# DOE_PCB_Schematics.net
KiCad netlist of a schematic drawn in EAGLE
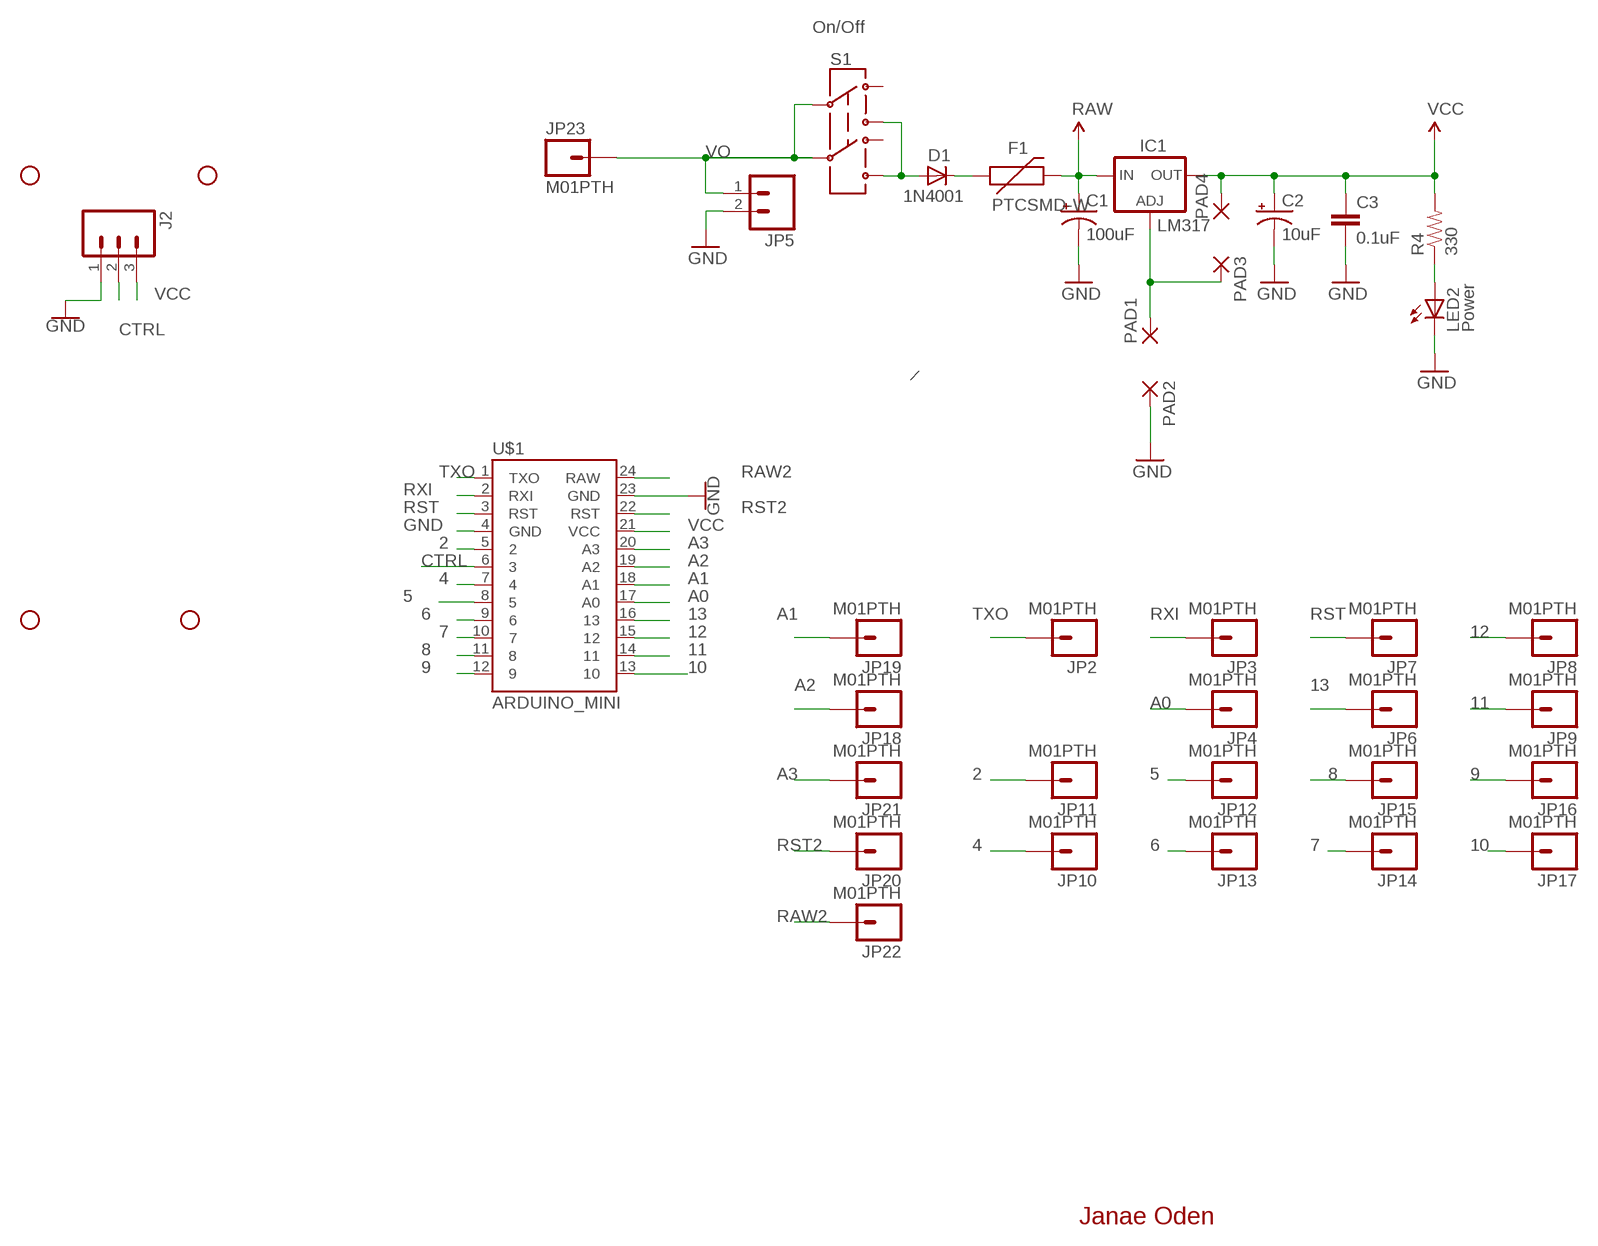
[diagram p0: schematic, sheet 1]

(export (version "E")
  (design (tool "Eeschema 10.0.6"))
  (components
    (comp (ref "C1")
      (value "100uF")
      (footprint "eagle-import:EIA7343")
      (libsource (lib "eagle-import") (part "CAP_POL7343"))
    )
    (comp (ref "C2")
      (value "10uF")
      (footprint "eagle-import:EIA3216")
      (libsource (lib "eagle-import") (part "CAP_POL1206"))
    )
    (comp (ref "C3")
      (value "0.1uF")
      (footprint "eagle-import:0603-CAP")
      (libsource (lib "eagle-import") (part "CAP0603-CAP"))
    )
    (comp (ref "D1")
      (value "1N4001")
      (footprint "eagle-import:SMA-DIODE-TYLERALT1")
      (libsource (lib "eagle-import") (part "DIODESMA-TYLERALT1"))
    )
    (comp (ref "F1")
      (value "PTCSMD-W")
      (footprint "eagle-import:PTC-1206-WIDE")
      (libsource (lib "eagle-import") (part "PTCSMD-W"))
    )
    (comp (ref "IC1")
      (value "LM317MBSTT3")
      (footprint "eagle-import:SOT223")
      (fields (field (name "PARTNUMBER") "LM317"))
      (libsource (lib "eagle-import") (part "LM317?MBSTT3"))
    )
    (comp (ref "J2")
      (value "M03SCREW")
      (footprint "eagle-import:SCREWTERMINAL-3.5MM-3")
      (libsource (lib "eagle-import") (part "M03SCREW"))
    )
    (comp (ref "JP2")
      (value "M01PTH")
      (footprint "eagle-import:1X01")
      (libsource (lib "eagle-import") (part "M01PTH"))
    )
    (comp (ref "JP3")
      (value "M01PTH")
      (footprint "eagle-import:1X01")
      (libsource (lib "eagle-import") (part "M01PTH"))
    )
    (comp (ref "JP4")
      (value "M01PTH")
      (footprint "eagle-import:1X01")
      (libsource (lib "eagle-import") (part "M01PTH"))
    )
    (comp (ref "JP5")
      (value "M02PTH")
      (footprint "eagle-import:1X02")
      (libsource (lib "eagle-import") (part "M02PTH"))
    )
    (comp (ref "JP6")
      (value "M01PTH")
      (footprint "eagle-import:1X01")
      (libsource (lib "eagle-import") (part "M01PTH"))
    )
    (comp (ref "JP7")
      (value "M01PTH")
      (footprint "eagle-import:1X01")
      (libsource (lib "eagle-import") (part "M01PTH"))
    )
    (comp (ref "JP8")
      (value "M01PTH")
      (footprint "eagle-import:1X01")
      (libsource (lib "eagle-import") (part "M01PTH"))
    )
    (comp (ref "JP9")
      (value "M01PTH")
      (footprint "eagle-import:1X01")
      (libsource (lib "eagle-import") (part "M01PTH"))
    )
    (comp (ref "JP10")
      (value "M01PTH")
      (footprint "eagle-import:1X01")
      (libsource (lib "eagle-import") (part "M01PTH"))
    )
    (comp (ref "JP11")
      (value "M01PTH")
      (footprint "eagle-import:1X01")
      (libsource (lib "eagle-import") (part "M01PTH"))
    )
    (comp (ref "JP12")
      (value "M01PTH")
      (footprint "eagle-import:1X01")
      (libsource (lib "eagle-import") (part "M01PTH"))
    )
    (comp (ref "JP13")
      (value "M01PTH")
      (footprint "eagle-import:1X01")
      (libsource (lib "eagle-import") (part "M01PTH"))
    )
    (comp (ref "JP14")
      (value "M01PTH")
      (footprint "eagle-import:1X01")
      (libsource (lib "eagle-import") (part "M01PTH"))
    )
    (comp (ref "JP15")
      (value "M01PTH")
      (footprint "eagle-import:1X01")
      (libsource (lib "eagle-import") (part "M01PTH"))
    )
    (comp (ref "JP16")
      (value "M01PTH")
      (footprint "eagle-import:1X01")
      (libsource (lib "eagle-import") (part "M01PTH"))
    )
    (comp (ref "JP17")
      (value "M01PTH")
      (footprint "eagle-import:1X01")
      (libsource (lib "eagle-import") (part "M01PTH"))
    )
    (comp (ref "JP18")
      (value "M01PTH")
      (footprint "eagle-import:1X01")
      (libsource (lib "eagle-import") (part "M01PTH"))
    )
    (comp (ref "JP19")
      (value "M01PTH")
      (footprint "eagle-import:1X01")
      (libsource (lib "eagle-import") (part "M01PTH"))
    )
    (comp (ref "JP20")
      (value "M01PTH")
      (footprint "eagle-import:1X01")
      (libsource (lib "eagle-import") (part "M01PTH"))
    )
    (comp (ref "JP21")
      (value "M01PTH")
      (footprint "eagle-import:1X01")
      (libsource (lib "eagle-import") (part "M01PTH"))
    )
    (comp (ref "JP22")
      (value "M01PTH")
      (footprint "eagle-import:1X01")
      (libsource (lib "eagle-import") (part "M01PTH"))
    )
    (comp (ref "JP23")
      (value "M01PTH")
      (footprint "eagle-import:1X01")
      (libsource (lib "eagle-import") (part "M01PTH"))
    )
    (comp (ref "LED2")
      (value "Power")
      (footprint "eagle-import:LED-1206")
      (libsource (lib "eagle-import") (part "LED1206"))
    )
    (comp (ref "PAD1")
      (value "1,6/0,8")
      (footprint "eagle-import:1,6_0,8")
      (libsource (lib "eagle-import") (part "1,6/0,8"))
    )
    (comp (ref "PAD2")
      (value "1,6/0,8")
      (footprint "eagle-import:1,6_0,8")
      (libsource (lib "eagle-import") (part "1,6/0,8"))
    )
    (comp (ref "PAD3")
      (value "1,6/0,8")
      (footprint "eagle-import:1,6_0,8")
      (libsource (lib "eagle-import") (part "1,6/0,8"))
    )
    (comp (ref "PAD4")
      (value "1,6/0,8")
      (footprint "eagle-import:1,6_0,8")
      (libsource (lib "eagle-import") (part "1,6/0,8"))
    )
    (comp (ref "R4")
      (value "330")
      (footprint "eagle-import:0603-RES")
      (libsource (lib "eagle-import") (part "RESISTOR0603-RES"))
    )
    (comp (ref "S1")
      (value "On/Off")
      (footprint "eagle-import:AYZ0202")
      (libsource (lib "eagle-import") (part "AYZ0202"))
    )
    (comp (ref "U$1")
      (value "ARDUINO_MINI")
      (footprint "eagle-import:ARDUINO_MINI")
      (libsource (lib "eagle-import") (part "ARDUINO_MINI"))
    )
    (comp (ref "U$3")
      (value "STAND-OFF")
      (footprint "eagle-import:STAND-OFF")
      (libsource (lib "eagle-import") (part "STAND-OFF"))
    )
    (comp (ref "U$4")
      (value "STAND-OFF")
      (footprint "eagle-import:STAND-OFF")
      (libsource (lib "eagle-import") (part "STAND-OFF"))
    )
    (comp (ref "U$5")
      (value "STAND-OFF")
      (footprint "eagle-import:STAND-OFF")
      (libsource (lib "eagle-import") (part "STAND-OFF"))
    )
    (comp (ref "U$7")
      (value "STAND-OFF")
      (footprint "eagle-import:STAND-OFF")
      (libsource (lib "eagle-import") (part "STAND-OFF"))
    )
  )
  (nets
    (net (code "1") (name "/2") (class "Default")
      (node (ref "JP11") (pin "1") (pinfunction "1_1") (pintype "passive"))
      (node (ref "U$1") (pin "5") (pinfunction "2_5") (pintype "bidirectional"))
    )
    (net (code "2") (name "/4") (class "Default")
      (node (ref "JP10") (pin "1") (pinfunction "1_1") (pintype "passive"))
      (node (ref "U$1") (pin "7") (pinfunction "4_7") (pintype "bidirectional"))
    )
    (net (code "3") (name "/5") (class "Default")
      (node (ref "JP12") (pin "1") (pinfunction "1_1") (pintype "passive"))
      (node (ref "U$1") (pin "8") (pinfunction "5_8") (pintype "bidirectional"))
    )
    (net (code "4") (name "/6") (class "Default")
      (node (ref "JP13") (pin "1") (pinfunction "1_1") (pintype "passive"))
      (node (ref "U$1") (pin "9") (pinfunction "6_9") (pintype "bidirectional"))
    )
    (net (code "5") (name "/7") (class "Default")
      (node (ref "JP14") (pin "1") (pinfunction "1_1") (pintype "passive"))
      (node (ref "U$1") (pin "10") (pinfunction "7_10") (pintype "bidirectional"))
    )
    (net (code "6") (name "/8") (class "Default")
      (node (ref "JP15") (pin "1") (pinfunction "1_1") (pintype "passive"))
      (node (ref "U$1") (pin "11") (pinfunction "8_11") (pintype "bidirectional"))
    )
    (net (code "7") (name "/9") (class "Default")
      (node (ref "JP16") (pin "1") (pinfunction "1_1") (pintype "passive"))
      (node (ref "U$1") (pin "12") (pinfunction "9_12") (pintype "bidirectional"))
    )
    (net (code "8") (name "/10") (class "Default")
      (node (ref "JP17") (pin "1") (pinfunction "1_1") (pintype "passive"))
      (node (ref "U$1") (pin "13") (pinfunction "10_13") (pintype "bidirectional"))
    )
    (net (code "9") (name "/11") (class "Default")
      (node (ref "JP9") (pin "1") (pinfunction "1_1") (pintype "passive"))
      (node (ref "U$1") (pin "14") (pinfunction "11_14") (pintype "bidirectional"))
    )
    (net (code "10") (name "/12") (class "Default")
      (node (ref "JP8") (pin "1") (pinfunction "1_1") (pintype "passive"))
      (node (ref "U$1") (pin "15") (pinfunction "12_15") (pintype "bidirectional"))
    )
    (net (code "11") (name "/13") (class "Default")
      (node (ref "JP6") (pin "1") (pinfunction "1_1") (pintype "passive"))
      (node (ref "U$1") (pin "16") (pinfunction "13_16") (pintype "bidirectional"))
    )
    (net (code "12") (name "/A0") (class "Default")
      (node (ref "JP4") (pin "1") (pinfunction "1_1") (pintype "passive"))
      (node (ref "U$1") (pin "17") (pinfunction "A0_17") (pintype "bidirectional"))
    )
    (net (code "13") (name "/A1") (class "Default")
      (node (ref "JP19") (pin "1") (pinfunction "1_1") (pintype "passive"))
      (node (ref "U$1") (pin "18") (pinfunction "A1_18") (pintype "bidirectional"))
    )
    (net (code "14") (name "/A2") (class "Default")
      (node (ref "JP18") (pin "1") (pinfunction "1_1") (pintype "passive"))
      (node (ref "U$1") (pin "19") (pinfunction "A2_19") (pintype "bidirectional"))
    )
    (net (code "15") (name "/A3") (class "Default")
      (node (ref "JP21") (pin "1") (pinfunction "1_1") (pintype "passive"))
      (node (ref "U$1") (pin "20") (pinfunction "A3_20") (pintype "bidirectional"))
    )
    (net (code "16") (name "/CTRL") (class "Default")
      (node (ref "J2") (pin "2") (pinfunction "2_2") (pintype "passive"))
      (node (ref "U$1") (pin "6") (pinfunction "3_6") (pintype "bidirectional"))
    )
    (net (code "17") (name "/RAW2") (class "Default")
      (node (ref "JP22") (pin "1") (pinfunction "1_1") (pintype "passive"))
      (node (ref "U$1") (pin "24") (pinfunction "RAW_24") (pintype "bidirectional"))
    )
    (net (code "18") (name "/RST") (class "Default")
      (node (ref "JP7") (pin "1") (pinfunction "1_1") (pintype "passive"))
      (node (ref "U$1") (pin "3") (pinfunction "RST_3") (pintype "bidirectional"))
    )
    (net (code "19") (name "/RST2") (class "Default")
      (node (ref "JP20") (pin "1") (pinfunction "1_1") (pintype "passive"))
      (node (ref "U$1") (pin "22") (pinfunction "RST_22") (pintype "bidirectional"))
    )
    (net (code "20") (name "/RXI") (class "Default")
      (node (ref "JP3") (pin "1") (pinfunction "1_1") (pintype "passive"))
      (node (ref "U$1") (pin "2") (pinfunction "RXI_2") (pintype "bidirectional"))
    )
    (net (code "21") (name "/TXO") (class "Default")
      (node (ref "JP2") (pin "1") (pinfunction "1_1") (pintype "passive"))
      (node (ref "U$1") (pin "1") (pinfunction "TXO_1") (pintype "bidirectional"))
    )
    (net (code "22") (name "/VO") (class "Default")
      (node (ref "JP23") (pin "1") (pinfunction "1_1") (pintype "passive"))
      (node (ref "JP5") (pin "1") (pinfunction "1_1") (pintype "passive"))
      (node (ref "S1") (pin "2") (pinfunction "2_2") (pintype "bidirectional"))
      (node (ref "S1") (pin "5") (pinfunction "5_5") (pintype "bidirectional"))
    )
    (net (code "23") (name "GND") (class "Default")
      (node (ref "C1") (pin "C") (pinfunction "-_C") (pintype "passive"))
      (node (ref "C2") (pin "C") (pinfunction "-_C") (pintype "passive"))
      (node (ref "C3") (pin "2") (pinfunction "2_2") (pintype "passive"))
      (node (ref "J2") (pin "1") (pinfunction "1_1") (pintype "passive"))
      (node (ref "JP5") (pin "2") (pinfunction "2_2") (pintype "passive"))
      (node (ref "LED2") (pin "C") (pinfunction "C_C") (pintype "passive"))
      (node (ref "PAD2") (pin "1") (pinfunction "P_1") (pintype "passive"))
      (node (ref "U$1") (pin "23") (pinfunction "GND_23") (pintype "bidirectional"))
      (node (ref "U$1") (pin "4") (pinfunction "GND_4") (pintype "bidirectional"))
    )
    (net (code "24") (name "Net-(D1-PadC)") (class "Default")
      (node (ref "D1") (pin "C") (pinfunction "C_C") (pintype "passive"))
      (node (ref "F1") (pin "1") (pinfunction "1_1") (pintype "bidirectional"))
    )
    (net (code "25") (name "Net-(IC1-ADJ)") (class "Default")
      (node (ref "IC1") (pin "1") (pinfunction "ADJ_1") (pintype "input"))
      (node (ref "PAD1") (pin "1") (pinfunction "P_1") (pintype "passive"))
      (node (ref "PAD3") (pin "1") (pinfunction "P_1") (pintype "passive"))
    )
    (net (code "26") (name "Net-(LED2-PadA)") (class "Default")
      (node (ref "LED2") (pin "A") (pinfunction "A_A") (pintype "passive"))
      (node (ref "R4") (pin "1") (pinfunction "1_1") (pintype "passive"))
    )
    (net (code "27") (name "Net-(S1-3)") (class "Default")
      (node (ref "D1") (pin "A") (pinfunction "A_A") (pintype "passive"))
      (node (ref "S1") (pin "1") (pinfunction "3_1") (pintype "bidirectional"))
      (node (ref "S1") (pin "4") (pinfunction "6_4") (pintype "bidirectional"))
    )
    (net (code "28") (name "RAW") (class "Default")
      (node (ref "C1") (pin "A") (pinfunction "+_A") (pintype "passive"))
      (node (ref "F1") (pin "2") (pinfunction "2_2") (pintype "bidirectional"))
      (node (ref "IC1") (pin "3") (pinfunction "IN_3") (pintype "input"))
    )
    (net (code "29") (name "VCC") (class "Default")
      (node (ref "C2") (pin "A") (pinfunction "+_A") (pintype "passive"))
      (node (ref "C3") (pin "1") (pinfunction "1_1") (pintype "passive"))
      (node (ref "IC1") (pin "4") (pinfunction "OUT_4") (pintype "passive"))
      (node (ref "J2") (pin "3") (pinfunction "3_3") (pintype "passive"))
      (node (ref "PAD4") (pin "1") (pinfunction "P_1") (pintype "passive"))
      (node (ref "R4") (pin "2") (pinfunction "2_2") (pintype "passive"))
      (node (ref "U$1") (pin "21") (pinfunction "VCC_21") (pintype "bidirectional"))
    )
    (net (code "30") (name "unconnected-(S1-1-Pad3)") (class "Default")
      (node (ref "S1") (pin "3") (pinfunction "1_3") (pintype "bidirectional"))
    )
    (net (code "31") (name "unconnected-(S1-4-Pad6)") (class "Default")
      (node (ref "S1") (pin "6") (pinfunction "4_6") (pintype "bidirectional"))
    )
  )
)
